# FilamentBox.net
KiCad netlist of a schematic drawn in EAGLE
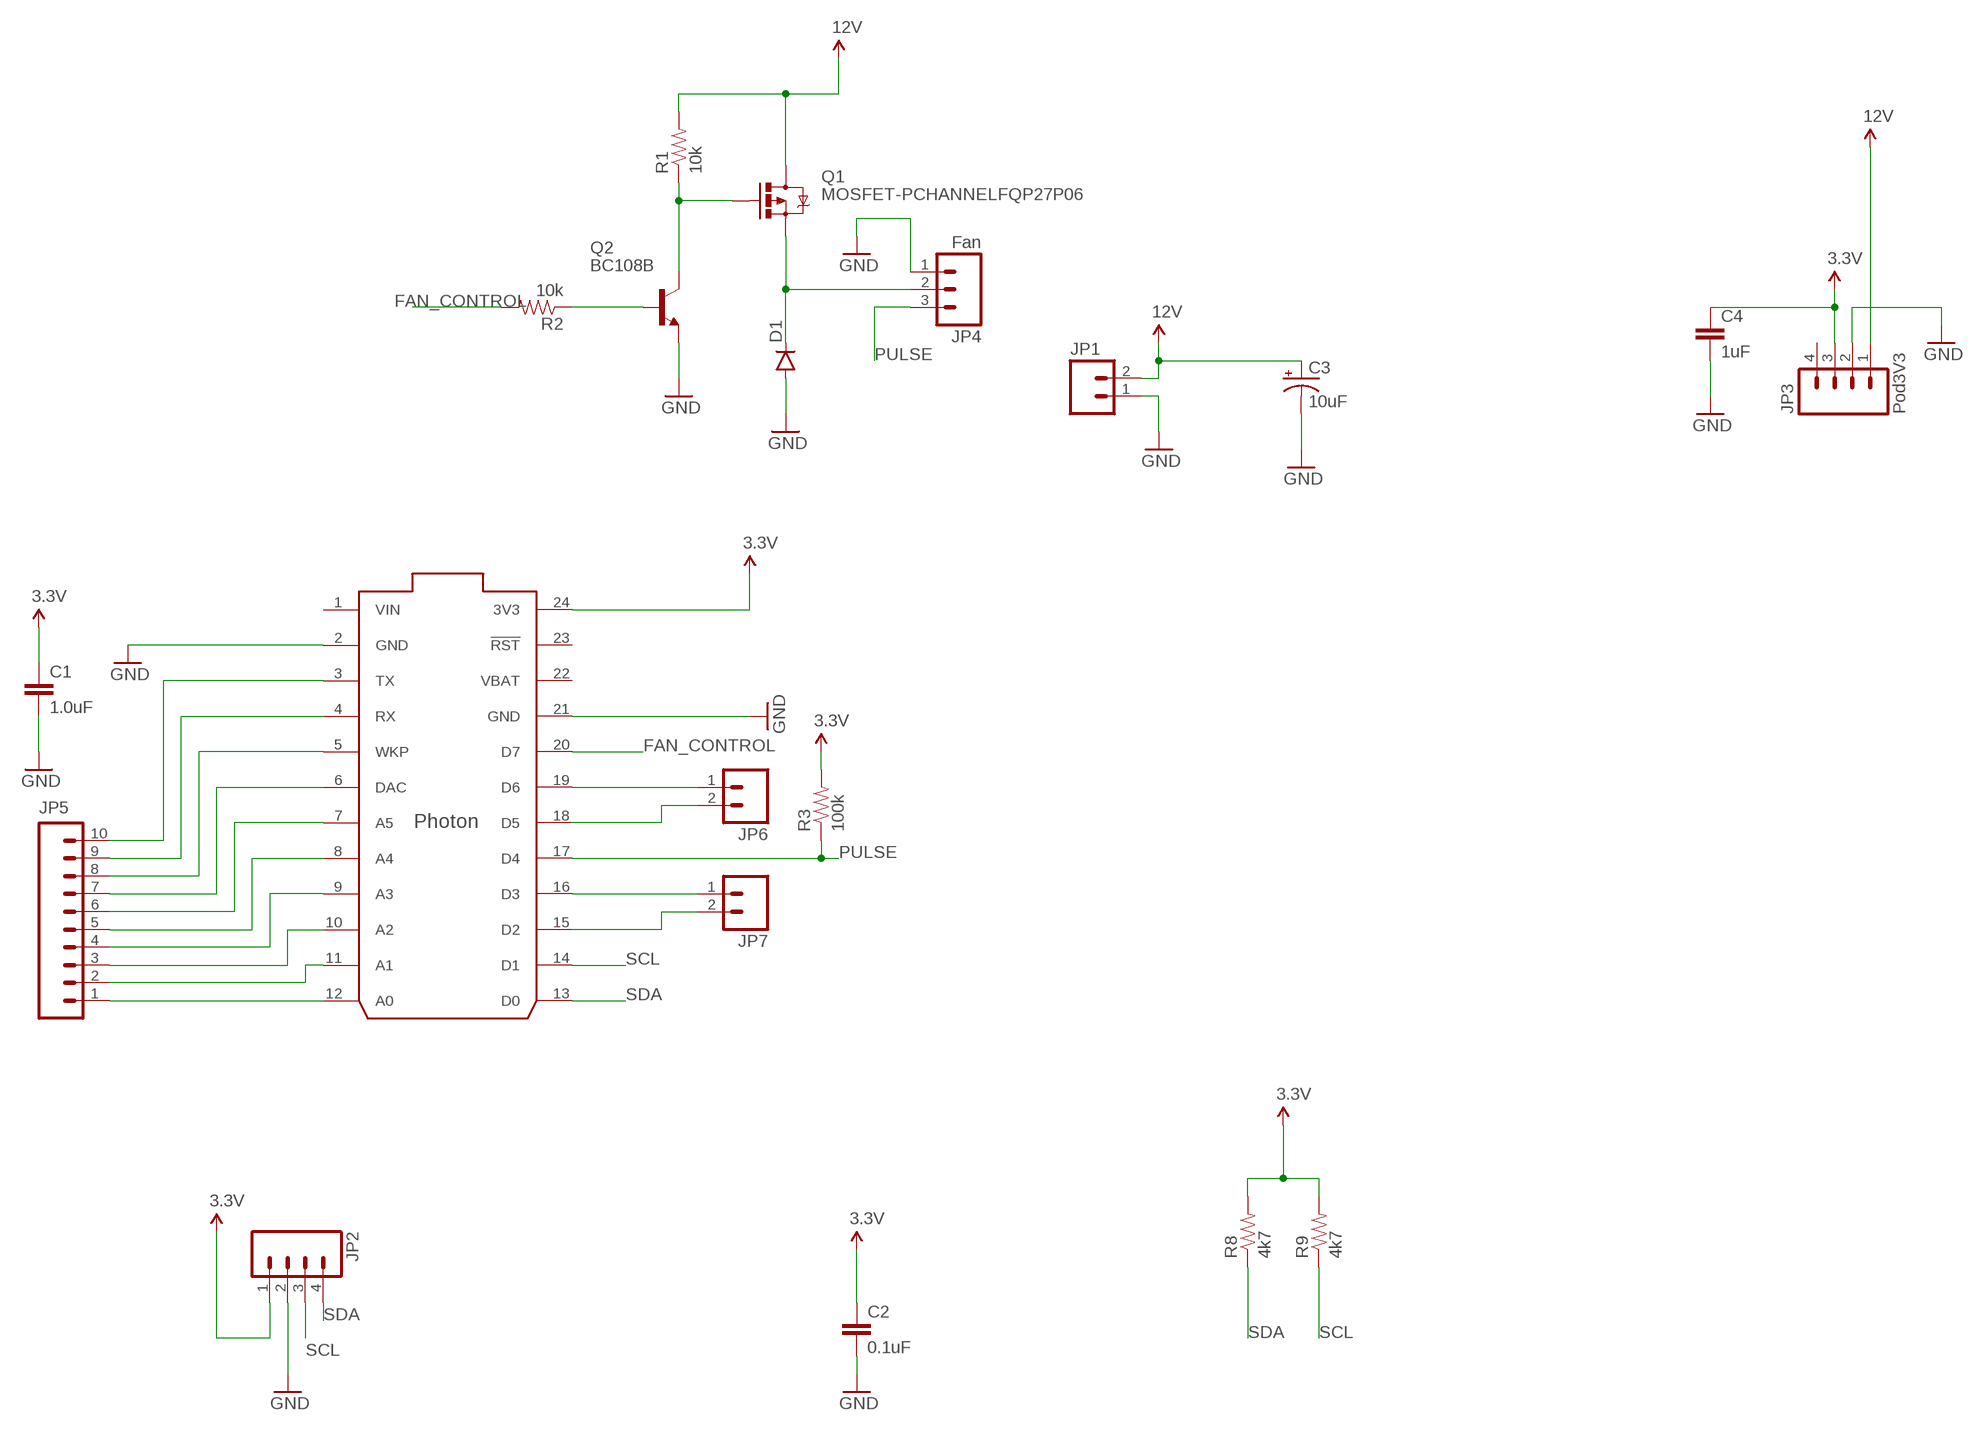
[diagram p0: schematic, sheet 1]

(export (version "E")
  (design (tool "Eeschema 10.0.6"))
  (components
    (comp (ref "C1")
      (value "1.0uF")
      (footprint "eagle-import:0805-CAP")
      (libsource (lib "eagle-import") (part "1.0UF-25V-+80/-20(0805){dblquote}"))
    )
    (comp (ref "C2")
      (value "0.1uF")
      (footprint "eagle-import:0805-CAP")
      (libsource (lib "eagle-import") (part "1.0UF-25V-+80/-20(0805){dblquote}"))
    )
    (comp (ref "C3")
      (value "10uF")
      (footprint "eagle-import:CPOL-RADIAL-10UF-25V")
      (libsource (lib "eagle-import") (part "CAP_POLPTH2"))
    )
    (comp (ref "C4")
      (value "1uF")
      (footprint "eagle-import:0805-CAP")
      (libsource (lib "eagle-import") (part "1UF-25V-10%(0805){dblquote}"))
    )
    (comp (ref "D1")
      (value "DIODESOD123")
      (footprint "eagle-import:SOD-123")
      (libsource (lib "eagle-import") (part "DIODESOD123"))
    )
    (comp (ref "JP1")
      (value "M02JST-PTH-2")
      (footprint "eagle-import:JST-2-PTH")
      (libsource (lib "eagle-import") (part "M02JST-PTH-2"))
    )
    (comp (ref "JP2")
      (value "M04PTH")
      (footprint "eagle-import:1X04")
      (libsource (lib "eagle-import") (part "M04PTH"))
    )
    (comp (ref "JP3")
      (value "Pod3V3")
      (footprint "eagle-import:1X04_NO_SILK_ALL_ROUND")
      (libsource (lib "eagle-import") (part "M04NO_SILK_ALL_ROUND"))
    )
    (comp (ref "JP4")
      (value "Fan")
      (footprint "eagle-import:MOLEX-1X3")
      (libsource (lib "eagle-import") (part "M03POLAR"))
    )
    (comp (ref "JP5")
      (value "M10NO_SILK_PTH_FEMALE")
      (footprint "eagle-import:1X10_NO_SILK")
      (libsource (lib "eagle-import") (part "M10NO_SILK_PTH_FEMALE"))
    )
    (comp (ref "JP6")
      (value "M021X02_NO_SILK")
      (footprint "eagle-import:1X02_NO_SILK")
      (libsource (lib "eagle-import") (part "M021X02_NO_SILK"))
    )
    (comp (ref "JP7")
      (value "M021X02_NO_SILK")
      (footprint "eagle-import:1X02_NO_SILK")
      (libsource (lib "eagle-import") (part "M021X02_NO_SILK"))
    )
    (comp (ref "Q1")
      (value "MOSFET-PCHANNELFQP27P06")
      (footprint "eagle-import:TO220V")
      (libsource (lib "eagle-import") (part "MOSFET-PCHANNELFQP27P06"))
    )
    (comp (ref "Q2")
      (value "BC108B")
      (footprint "eagle-import:TO18")
      (libsource (lib "eagle-import") (part "BC108B"))
    )
    (comp (ref "R1")
      (value "10k")
      (footprint "eagle-import:0805")
      (libsource (lib "eagle-import") (part "RESISTOR0805-RES"))
    )
    (comp (ref "R2")
      (value "10k")
      (footprint "eagle-import:0805")
      (libsource (lib "eagle-import") (part "RESISTOR0805-RES"))
    )
    (comp (ref "R3")
      (value "100k")
      (footprint "eagle-import:0805")
      (libsource (lib "eagle-import") (part "RESISTOR0805-RES"))
    )
    (comp (ref "R8")
      (value "4k7")
      (footprint "eagle-import:0805")
      (libsource (lib "eagle-import") (part "RESISTOR0805-RES"))
    )
    (comp (ref "R9")
      (value "4k7")
      (footprint "eagle-import:0805")
      (libsource (lib "eagle-import") (part "RESISTOR0805-RES"))
    )
    (comp (ref "U3")
      (value "PHOTON")
      (footprint "eagle-import:PHOTON")
      (libsource (lib "eagle-import") (part "PHOTON_WITH_HEADERS"))
    )
  )
  (nets
    (net (code "1") (name "/FAN_CONTROL") (class "Default")
      (node (ref "R2") (pin "2") (pinfunction "2_2") (pintype "passive"))
      (node (ref "U3") (pin "20") (pinfunction "D7_20") (pintype "bidirectional"))
    )
    (net (code "2") (name "/PULSE") (class "Default")
      (node (ref "JP4") (pin "3") (pinfunction "3_3") (pintype "passive"))
      (node (ref "R3") (pin "1") (pinfunction "1_1") (pintype "passive"))
      (node (ref "U3") (pin "17") (pinfunction "D4_17") (pintype "bidirectional"))
    )
    (net (code "3") (name "/SCL") (class "Default")
      (node (ref "JP2") (pin "3") (pinfunction "3_3") (pintype "passive"))
      (node (ref "R9") (pin "1") (pinfunction "1_1") (pintype "passive"))
      (node (ref "U3") (pin "14") (pinfunction "D1_14") (pintype "bidirectional"))
    )
    (net (code "4") (name "/SDA") (class "Default")
      (node (ref "JP2") (pin "4") (pinfunction "4_4") (pintype "passive"))
      (node (ref "R8") (pin "1") (pinfunction "1_1") (pintype "passive"))
      (node (ref "U3") (pin "13") (pinfunction "D0_13") (pintype "bidirectional"))
    )
    (net (code "5") (name "/VBAT") (class "Default")
      (node (ref "U3") (pin "22") (pinfunction "VBAT_22") (pintype "power_in"))
    )
    (net (code "6") (name "/VIN") (class "Default")
      (node (ref "U3") (pin "1") (pinfunction "VIN_1") (pintype "power_in"))
    )
    (net (code "7") (name "3.3V") (class "Default")
      (node (ref "C1") (pin "1") (pinfunction "1_1") (pintype "passive"))
      (node (ref "C2") (pin "1") (pinfunction "1_1") (pintype "passive"))
      (node (ref "C4") (pin "1") (pinfunction "1_1") (pintype "passive"))
      (node (ref "JP2") (pin "1") (pinfunction "1_1") (pintype "passive"))
      (node (ref "JP3") (pin "3") (pinfunction "3_3") (pintype "passive"))
      (node (ref "R3") (pin "2") (pinfunction "2_2") (pintype "passive"))
      (node (ref "R8") (pin "2") (pinfunction "2_2") (pintype "passive"))
      (node (ref "R9") (pin "2") (pinfunction "2_2") (pintype "passive"))
      (node (ref "U3") (pin "24") (pinfunction "3V3_24") (pintype "power_in"))
    )
    (net (code "8") (name "12V") (class "Default")
      (node (ref "C3") (pin "1") (pinfunction "+_1") (pintype "passive"))
      (node (ref "JP1") (pin "2") (pinfunction "2_2") (pintype "passive"))
      (node (ref "JP3") (pin "1") (pinfunction "1_1") (pintype "passive"))
      (node (ref "Q1") (pin "2") (pinfunction "D_2") (pintype "passive"))
      (node (ref "R1") (pin "2") (pinfunction "2_2") (pintype "passive"))
    )
    (net (code "9") (name "GND") (class "Default")
      (node (ref "C1") (pin "2") (pinfunction "2_2") (pintype "passive"))
      (node (ref "C2") (pin "2") (pinfunction "2_2") (pintype "passive"))
      (node (ref "C3") (pin "2") (pinfunction "-_2") (pintype "passive"))
      (node (ref "C4") (pin "2") (pinfunction "2_2") (pintype "passive"))
      (node (ref "D1") (pin "A") (pinfunction "A_A") (pintype "passive"))
      (node (ref "JP1") (pin "1") (pinfunction "1_1") (pintype "passive"))
      (node (ref "JP2") (pin "2") (pinfunction "2_2") (pintype "passive"))
      (node (ref "JP3") (pin "2") (pinfunction "2_2") (pintype "passive"))
      (node (ref "JP4") (pin "1") (pinfunction "1_1") (pintype "passive"))
      (node (ref "Q2") (pin "1") (pinfunction "E_1") (pintype "passive"))
      (node (ref "U3") (pin "2") (pinfunction "GND_2") (pintype "power_in"))
      (node (ref "U3") (pin "21") (pinfunction "GND_21") (pintype "power_in"))
    )
    (net (code "10") (name "Net-(Q1-G)") (class "Default")
      (node (ref "Q1") (pin "1") (pinfunction "G_1") (pintype "passive"))
      (node (ref "Q2") (pin "3") (pinfunction "C_3") (pintype "passive"))
      (node (ref "R1") (pin "1") (pinfunction "1_1") (pintype "passive"))
    )
    (net (code "11") (name "Net-(Q1-S)") (class "Default")
      (node (ref "D1") (pin "C") (pinfunction "C_C") (pintype "passive"))
      (node (ref "JP4") (pin "2") (pinfunction "2_2") (pintype "passive"))
      (node (ref "Q1") (pin "3") (pinfunction "S_3") (pintype "passive"))
    )
    (net (code "12") (name "Net-(Q2-B)") (class "Default")
      (node (ref "Q2") (pin "2") (pinfunction "B_2") (pintype "passive"))
      (node (ref "R2") (pin "1") (pinfunction "1_1") (pintype "passive"))
    )
    (net (code "13") (name "Net-(U3-A0)") (class "Default")
      (node (ref "JP5") (pin "1") (pinfunction "1_1") (pintype "passive"))
      (node (ref "U3") (pin "12") (pinfunction "A0_12") (pintype "bidirectional"))
    )
    (net (code "14") (name "Net-(U3-A1)") (class "Default")
      (node (ref "JP5") (pin "2") (pinfunction "2_2") (pintype "passive"))
      (node (ref "U3") (pin "11") (pinfunction "A1_11") (pintype "bidirectional"))
    )
    (net (code "15") (name "Net-(U3-A2)") (class "Default")
      (node (ref "JP5") (pin "3") (pinfunction "3_3") (pintype "passive"))
      (node (ref "U3") (pin "10") (pinfunction "A2_10") (pintype "bidirectional"))
    )
    (net (code "16") (name "Net-(U3-A3)") (class "Default")
      (node (ref "JP5") (pin "4") (pinfunction "4_4") (pintype "passive"))
      (node (ref "U3") (pin "9") (pinfunction "A3_9") (pintype "bidirectional"))
    )
    (net (code "17") (name "Net-(U3-A4)") (class "Default")
      (node (ref "JP5") (pin "5") (pinfunction "5_5") (pintype "passive"))
      (node (ref "U3") (pin "8") (pinfunction "A4_8") (pintype "bidirectional"))
    )
    (net (code "18") (name "Net-(U3-A5)") (class "Default")
      (node (ref "JP5") (pin "6") (pinfunction "6_6") (pintype "passive"))
      (node (ref "U3") (pin "7") (pinfunction "A5_7") (pintype "bidirectional"))
    )
    (net (code "19") (name "Net-(U3-D2)") (class "Default")
      (node (ref "JP7") (pin "2") (pinfunction "2_2") (pintype "passive"))
      (node (ref "U3") (pin "15") (pinfunction "D2_15") (pintype "bidirectional"))
    )
    (net (code "20") (name "Net-(U3-D3)") (class "Default")
      (node (ref "JP7") (pin "1") (pinfunction "1_1") (pintype "passive"))
      (node (ref "U3") (pin "16") (pinfunction "D3_16") (pintype "bidirectional"))
    )
    (net (code "21") (name "Net-(U3-D5)") (class "Default")
      (node (ref "JP6") (pin "2") (pinfunction "2_2") (pintype "passive"))
      (node (ref "U3") (pin "18") (pinfunction "D5_18") (pintype "bidirectional"))
    )
    (net (code "22") (name "Net-(U3-D6)") (class "Default")
      (node (ref "JP6") (pin "1") (pinfunction "1_1") (pintype "passive"))
      (node (ref "U3") (pin "19") (pinfunction "D6_19") (pintype "bidirectional"))
    )
    (net (code "23") (name "Net-(U3-DAC)") (class "Default")
      (node (ref "JP5") (pin "7") (pinfunction "7_7") (pintype "passive"))
      (node (ref "U3") (pin "6") (pinfunction "DAC_6") (pintype "bidirectional"))
    )
    (net (code "24") (name "Net-(U3-RX)") (class "Default")
      (node (ref "JP5") (pin "9") (pinfunction "9_9") (pintype "passive"))
      (node (ref "U3") (pin "4") (pinfunction "RX_4") (pintype "bidirectional"))
    )
    (net (code "25") (name "Net-(U3-TX)") (class "Default")
      (node (ref "JP5") (pin "10") (pinfunction "10_10") (pintype "passive"))
      (node (ref "U3") (pin "3") (pinfunction "TX_3") (pintype "bidirectional"))
    )
    (net (code "26") (name "Net-(U3-WKP)") (class "Default")
      (node (ref "JP5") (pin "8") (pinfunction "8_8") (pintype "passive"))
      (node (ref "U3") (pin "5") (pinfunction "WKP_5") (pintype "bidirectional"))
    )
    (net (code "27") (name "unconnected-(JP3-Pad4)") (class "Default")
      (node (ref "JP3") (pin "4") (pinfunction "4_4") (pintype "passive"))
    )
    (net (code "28") (name "unconnected-(U3-~{RST}-Pad23)") (class "Default")
      (node (ref "U3") (pin "23") (pinfunction "~{RST}_23") (pintype "bidirectional"))
    )
  )
)
